# POWER.net
KiCad netlist of a schematic drawn in Altium Designer
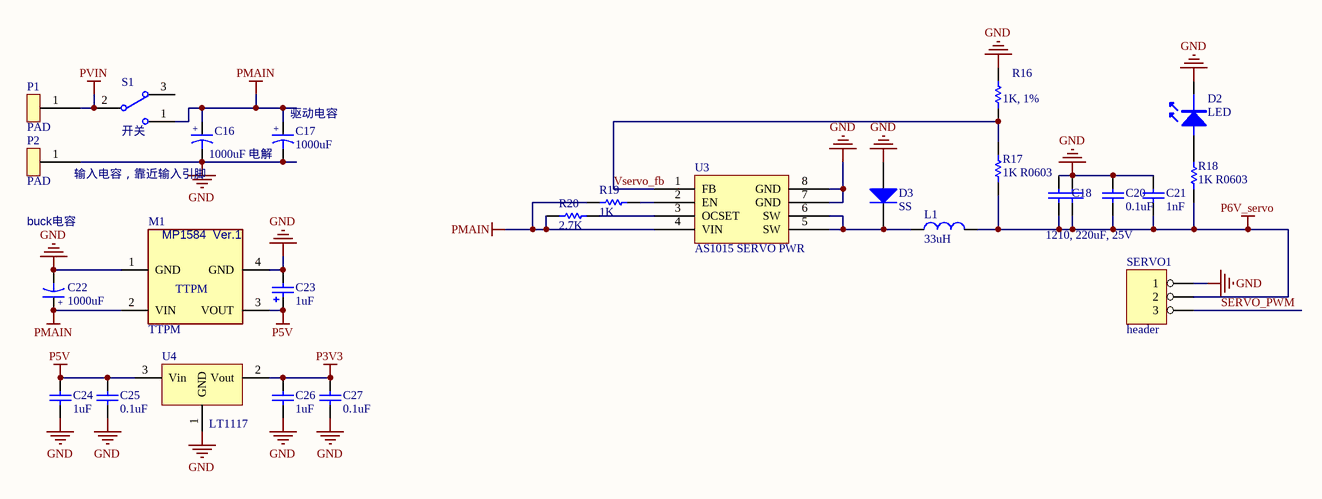
[diagram p0: POWER.SchDoc]

(export (version "E")
  (design (tool "Eeschema 10.0.6"))
  (components
    (comp (ref "C16")
      (value "1000uF 电解")
      (footprint "CAP_1000x2000")
      (libsource (lib "My Footprint") (part "CAP1"))
    )
    (comp (ref "C17")
      (value "1000uF")
      (footprint "CAP_1000x2000")
      (libsource (lib "My Footprint") (part "CAP1"))
    )
    (comp (ref "C18")
      (value "1210, 220uF, 25V")
      (footprint "CAP_1000x2000")
      (description "Capacitor")
      (fields (field (name "PUBLISHER") "Altium Limited"))
      (libsource (lib "My Footprint") (part "CAP"))
    )
    (comp (ref "C19")
      (value "1210, 220uF, 25V")
      (footprint "C1210")
      (description "Capacitor")
      (fields (field (name "PUBLISHER") "Altium Limited"))
      (libsource (lib "My Footprint") (part "CAP"))
    )
    (comp (ref "C20")
      (value "0.1uF")
      (footprint "0603_C")
      (description "Capacitor")
      (fields (field (name "PUBLISHER") "Altium Limited"))
      (libsource (lib "My Footprint") (part "CAP"))
    )
    (comp (ref "C21")
      (value "1nF")
      (footprint "C1206")
      (description "Capacitor")
      (fields (field (name "PUBLISHER") "Altium Limited"))
      (libsource (lib "My Footprint") (part "CAP"))
    )
    (comp (ref "C22")
      (value "1000uF")
      (footprint "CAP_1000x2000")
      (libsource (lib "My Footprint") (part "CAP1"))
    )
    (comp (ref "C23")
      (value "1uF")
      (footprint "CAPC6032C")
      (description "Capacitor")
      (fields (field (name "PUBLISHER") "Altium Limited"))
      (libsource (lib "My Footprint") (part "CAP_tan"))
    )
    (comp (ref "C24")
      (value "1uF")
      (footprint "0805_c")
      (description "Capacitor")
      (fields (field (name "PUBLISHER") "Altium Limited"))
      (libsource (lib "My Footprint") (part "CAP"))
    )
    (comp (ref "C25")
      (value "0.1uF")
      (footprint "0603_C")
      (description "Capacitor")
      (fields (field (name "PUBLISHER") "Altium Limited"))
      (libsource (lib "My Footprint") (part "CAP"))
    )
    (comp (ref "C26")
      (value "1uF")
      (footprint "0805_c")
      (description "Capacitor")
      (fields (field (name "PUBLISHER") "Altium Limited"))
      (libsource (lib "My Footprint") (part "CAP"))
    )
    (comp (ref "C27")
      (value "0.1uF")
      (footprint "0603_C")
      (description "Capacitor")
      (fields (field (name "PUBLISHER") "Altium Limited"))
      (libsource (lib "My Footprint") (part "CAP"))
    )
    (comp (ref "D2")
      (value "LED")
      (footprint "0603_LED")
      (description "LED 发光二极管")
      (libsource (lib "My Footprint") (part "LED"))
    )
    (comp (ref "D3") (value "SS") (footprint "DO-214AC(") (libsource (lib "My Footprint") (part "SS24")))
    (comp (ref "L1") (value "33uH") (footprint "L 5x5") (libsource (lib "My Footprint") (part "Inductor")))
    (comp (ref "M1") (value "TTPM") (footprint "TTPM_1") (libsource (lib "SamacSys") (part "TT_PWR_MOD")))
    (comp (ref "P1") (value "PAD") (footprint "PAD_BIG") (libsource (lib "My Footprint") (part "PAD")))
    (comp (ref "P2") (value "PAD") (footprint "PAD_BIG") (libsource (lib "My Footprint") (part "PAD")))
    (comp (ref "R16")
      (value "1K, 1%")
      (footprint "0603_R")
      (description "Resistor")
      (fields (field (name "PUBLISHER") "Altium Limited"))
      (libsource (lib "My Footprint") (part "RES0"))
    )
    (comp (ref "R17")
      (value "1K R0603")
      (footprint "0603_R")
      (description "Resistor")
      (fields (field (name "PUBLISHER") "Altium Limited"))
      (libsource (lib "My Footprint") (part "RES"))
    )
    (comp (ref "R18")
      (value "1K R0603")
      (footprint "0603_R")
      (description "Resistor")
      (fields (field (name "PUBLISHER") "Altium Limited"))
      (libsource (lib "My Footprint") (part "RES"))
    )
    (comp (ref "R19")
      (value "1K")
      (footprint "0603_R")
      (description "Resistor")
      (fields (field (name "PUBLISHER") "Altium Limited"))
      (libsource (lib "My Footprint") (part "RES0"))
    )
    (comp (ref "R20")
      (value "2.7K")
      (footprint "0603_R")
      (description "Resistor")
      (fields (field (name "PUBLISHER") "Altium Limited"))
      (libsource (lib "My Footprint") (part "RES0"))
    )
    (comp (ref "S1") (value "开关") (footprint "拨动开关") (libsource (lib "My Footprint") (part "switch 3")))
    (comp (ref "SERVO1")
      (value "header")
      (footprint "header3")
      (libsource (lib "My Footprint") (part "HEADER 3"))
    )
    (comp (ref "U3")
      (value "AS1015 SERVO PWR")
      (footprint "SOIC-8")
      (libsource (lib "My Footprint") (part "AS1015"))
    )
    (comp (ref "U4")
      (value "LT1117")
      (footprint "SOT-223")
      (description "3.3V电压转换器AMS1117")
      (libsource (lib "My Footprint") (part "AMS1117"))
    )
  )
  (nets
    (net (code "1") (name "/SERVO_PWM") (class "Default")
      (node (ref "SERVO1") (pin "3") (pinfunction "3_3") (pintype "passive"))
    )
    (net (code "2") (name "/Vservo_fb") (class "Default")
      (node (ref "R16") (pin "1") (pinfunction "1_1") (pintype "passive"))
      (node (ref "R17") (pin "2") (pinfunction "2_2") (pintype "passive"))
      (node (ref "U3") (pin "1") (pinfunction "FB_1") (pintype "passive"))
    )
    (net (code "3") (name "GND") (class "Default")
      (node (ref "C16") (pin "2") (pinfunction "2_2") (pintype "passive"))
      (node (ref "C17") (pin "2") (pinfunction "2_2") (pintype "passive"))
      (node (ref "C18") (pin "2") (pinfunction "2_2") (pintype "passive"))
      (node (ref "C19") (pin "2") (pinfunction "2_2") (pintype "passive"))
      (node (ref "C20") (pin "2") (pinfunction "2_2") (pintype "passive"))
      (node (ref "C21") (pin "2") (pinfunction "2_2") (pintype "passive"))
      (node (ref "C22") (pin "2") (pinfunction "2_2") (pintype "passive"))
      (node (ref "C23") (pin "2") (pinfunction "2_2") (pintype "passive"))
      (node (ref "C24") (pin "1") (pinfunction "1_1") (pintype "passive"))
      (node (ref "C25") (pin "1") (pinfunction "1_1") (pintype "passive"))
      (node (ref "C26") (pin "1") (pinfunction "1_1") (pintype "passive"))
      (node (ref "C27") (pin "1") (pinfunction "1_1") (pintype "passive"))
      (node (ref "D2") (pin "2") (pinfunction "K_2") (pintype "passive"))
      (node (ref "D3") (pin "1") (pinfunction "A_1") (pintype "passive"))
      (node (ref "M1") (pin "1") (pinfunction "GND_1") (pintype "passive"))
      (node (ref "M1") (pin "4") (pinfunction "GND_4") (pintype "passive"))
      (node (ref "P2") (pin "1") (pintype "passive"))
      (node (ref "R16") (pin "2") (pinfunction "2_2") (pintype "passive"))
      (node (ref "SERVO1") (pin "1") (pinfunction "1_1") (pintype "passive"))
      (node (ref "U3") (pin "7") (pinfunction "GND_7") (pintype "passive"))
      (node (ref "U3") (pin "8") (pinfunction "GND_8") (pintype "passive"))
      (node (ref "U4") (pin "1") (pinfunction "GND_1") (pintype "passive"))
    )
    (net (code "4") (name "Net-(D2-A)") (class "Default")
      (node (ref "D2") (pin "1") (pinfunction "A_1") (pintype "passive"))
      (node (ref "R18") (pin "2") (pinfunction "2_2") (pintype "passive"))
    )
    (net (code "5") (name "Net-(D3-K)") (class "Default")
      (node (ref "D3") (pin "2") (pinfunction "K_2") (pintype "passive"))
      (node (ref "L1") (pin "1") (pinfunction "1_1") (pintype "passive"))
      (node (ref "U3") (pin "5") (pinfunction "SW_5") (pintype "passive"))
      (node (ref "U3") (pin "6") (pinfunction "SW_6") (pintype "passive"))
    )
    (net (code "6") (name "Net-(U3-EN)") (class "Default")
      (node (ref "R19") (pin "2") (pinfunction "2_2") (pintype "passive"))
      (node (ref "U3") (pin "2") (pinfunction "EN_2") (pintype "passive"))
    )
    (net (code "7") (name "Net-(U3-OCSET)") (class "Default")
      (node (ref "R20") (pin "2") (pinfunction "2_2") (pintype "passive"))
      (node (ref "U3") (pin "3") (pinfunction "OCSET_3") (pintype "passive"))
    )
    (net (code "8") (name "P3V3") (class "Default")
      (node (ref "C26") (pin "2") (pinfunction "2_2") (pintype "passive"))
      (node (ref "C27") (pin "2") (pinfunction "2_2") (pintype "passive"))
      (node (ref "U4") (pin "2") (pinfunction "Vout_2") (pintype "passive"))
    )
    (net (code "9") (name "P5V") (class "Default")
      (node (ref "C23") (pin "1") (pinfunction "1_1") (pintype "passive"))
      (node (ref "C24") (pin "2") (pinfunction "2_2") (pintype "passive"))
      (node (ref "C25") (pin "2") (pinfunction "2_2") (pintype "passive"))
      (node (ref "M1") (pin "3") (pinfunction "VOUT_3") (pintype "passive"))
      (node (ref "U4") (pin "3") (pinfunction "Vin_3") (pintype "passive"))
    )
    (net (code "10") (name "P6V_servo") (class "Default")
      (node (ref "C18") (pin "1") (pinfunction "1_1") (pintype "passive"))
      (node (ref "C19") (pin "1") (pinfunction "1_1") (pintype "passive"))
      (node (ref "C20") (pin "1") (pinfunction "1_1") (pintype "passive"))
      (node (ref "C21") (pin "1") (pinfunction "1_1") (pintype "passive"))
      (node (ref "L1") (pin "2") (pinfunction "2_2") (pintype "passive"))
      (node (ref "R17") (pin "1") (pinfunction "1_1") (pintype "passive"))
      (node (ref "R18") (pin "1") (pinfunction "1_1") (pintype "passive"))
      (node (ref "SERVO1") (pin "2") (pinfunction "2_2") (pintype "passive"))
    )
    (net (code "11") (name "PMAIN") (class "Default")
      (node (ref "C16") (pin "1") (pinfunction "1_1") (pintype "passive"))
      (node (ref "C17") (pin "1") (pinfunction "1_1") (pintype "passive"))
      (node (ref "C22") (pin "1") (pinfunction "1_1") (pintype "passive"))
      (node (ref "M1") (pin "2") (pinfunction "VIN_2") (pintype "passive"))
      (node (ref "R19") (pin "1") (pinfunction "1_1") (pintype "passive"))
      (node (ref "R20") (pin "1") (pinfunction "1_1") (pintype "passive"))
      (node (ref "S1") (pin "1") (pinfunction "1_1") (pintype "passive"))
      (node (ref "U3") (pin "4") (pinfunction "VIN_4") (pintype "passive"))
    )
    (net (code "12") (name "PVIN") (class "Default")
      (node (ref "P1") (pin "1") (pintype "passive"))
      (node (ref "S1") (pin "2") (pinfunction "2_2") (pintype "passive"))
    )
    (net (code "13") (name "unconnected-(S1-Pad3)") (class "Default")
      (node (ref "S1") (pin "3") (pinfunction "3_3") (pintype "passive"))
    )
  )
)
